# EasyEDA_Audio_Amp.net
KiCad netlist of a schematic drawn in EasyEDA Pro
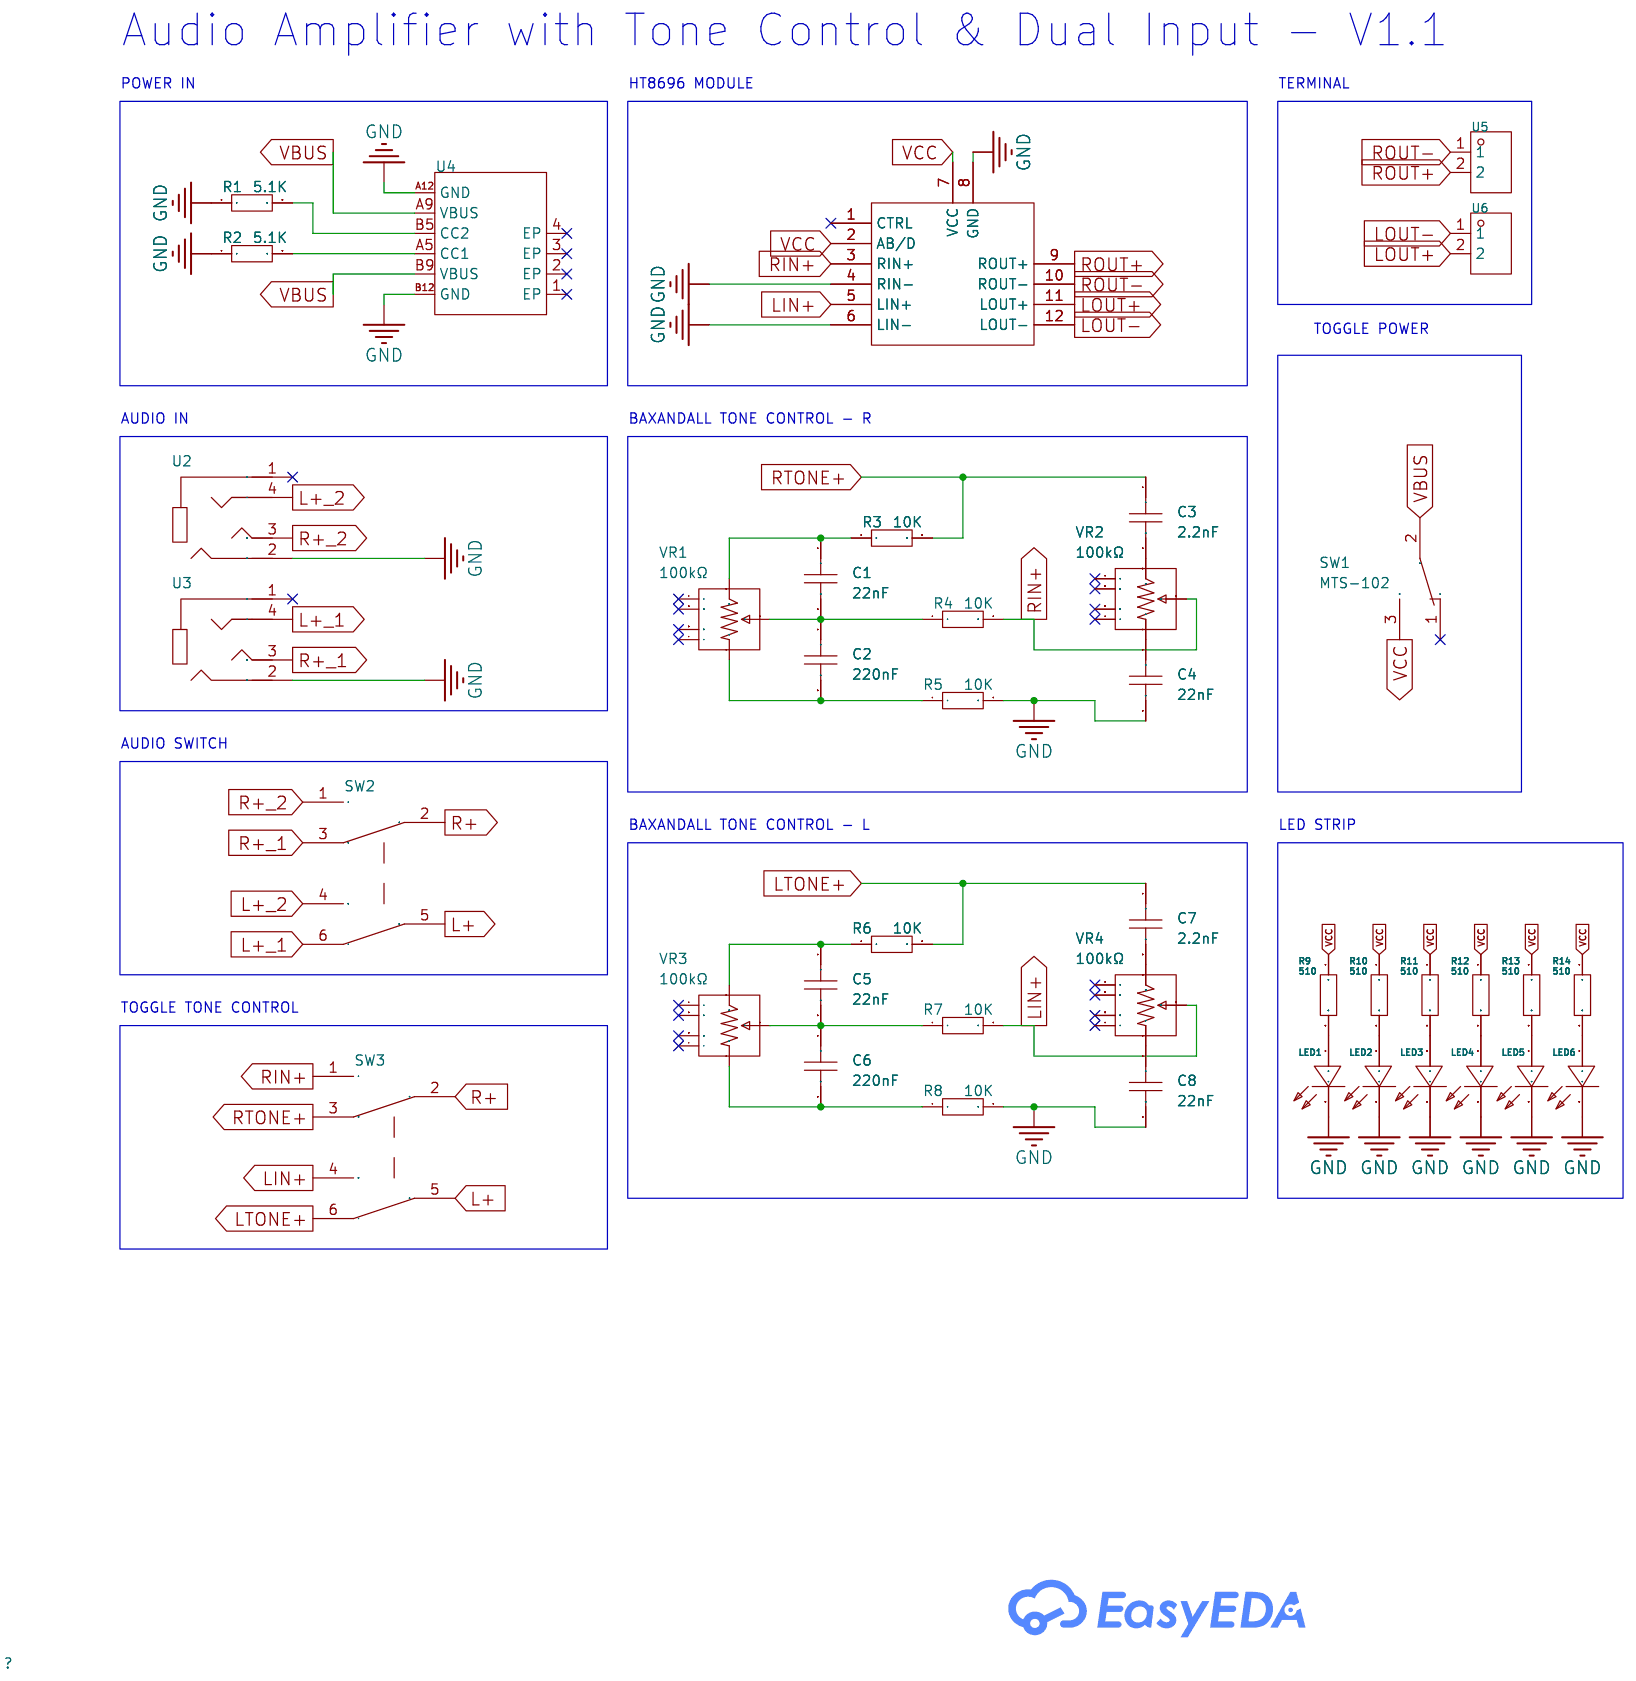
[diagram p0: schematic sheet]

(export (version "E")
  (design (tool "Eeschema 10.0.6"))
  (components
    (comp (ref "C1")
      (value "22nF")
      (footprint "easyedapro:C0603")
      (libsource (lib "easyedapro") (part "CAP_OLD"))
    )
    (comp (ref "C2")
      (value "220nF")
      (footprint "easyedapro:C0603")
      (libsource (lib "easyedapro") (part "CAP_OLD"))
    )
    (comp (ref "C3")
      (value "2.2nF")
      (footprint "easyedapro:C0603")
      (libsource (lib "easyedapro") (part "CAP_OLD"))
    )
    (comp (ref "C4")
      (value "22nF")
      (footprint "easyedapro:C0603")
      (libsource (lib "easyedapro") (part "CAP_OLD"))
    )
    (comp (ref "C5")
      (value "22nF")
      (footprint "easyedapro:C0603")
      (libsource (lib "easyedapro") (part "CAP_OLD"))
    )
    (comp (ref "C6")
      (value "220nF")
      (footprint "easyedapro:C0603")
      (libsource (lib "easyedapro") (part "CAP_OLD"))
    )
    (comp (ref "C7")
      (value "2.2nF")
      (footprint "easyedapro:C0603")
      (libsource (lib "easyedapro") (part "CAP_OLD"))
    )
    (comp (ref "C8")
      (value "22nF")
      (footprint "easyedapro:C0603")
      (libsource (lib "easyedapro") (part "CAP_OLD"))
    )
    (comp (ref "LED1")
      (value "KT-0805G")
      (footprint "easyedapro:LED0805-R-RD")
      (fields (field (name "Manufacturer") "KENTO"))
      (libsource (lib "easyedapro") (part "Led Rosso 0805"))
    )
    (comp (ref "LED2")
      (value "KT-0805G")
      (footprint "easyedapro:LED0805-R-RD")
      (fields (field (name "Manufacturer") "KENTO"))
      (libsource (lib "easyedapro") (part "Led Rosso 0805"))
    )
    (comp (ref "LED3")
      (value "KT-0805G")
      (footprint "easyedapro:LED0805-R-RD")
      (fields (field (name "Manufacturer") "KENTO"))
      (libsource (lib "easyedapro") (part "Led Rosso 0805"))
    )
    (comp (ref "LED4")
      (value "KT-0805G")
      (footprint "easyedapro:LED0805-R-RD")
      (fields (field (name "Manufacturer") "KENTO"))
      (libsource (lib "easyedapro") (part "Led Rosso 0805"))
    )
    (comp (ref "LED5")
      (value "KT-0805G")
      (footprint "easyedapro:LED0805-R-RD")
      (fields (field (name "Manufacturer") "KENTO"))
      (libsource (lib "easyedapro") (part "Led Rosso 0805"))
    )
    (comp (ref "LED6")
      (value "KT-0805G")
      (footprint "easyedapro:LED0805-R-RD")
      (fields (field (name "Manufacturer") "KENTO"))
      (libsource (lib "easyedapro") (part "Led Rosso 0805"))
    )
    (comp (ref "R1")
      (value "5.1K")
      (footprint "easyedapro:R0603")
      (fields
        (field (name "Manufacturer Part") "0805W8F2002T5E")
        (field (name "Manufacturer") "UNI-ROYAL(厚声)")
      )
      (libsource (lib "easyedapro") (part "Res"))
    )
    (comp (ref "R2")
      (value "5.1K")
      (footprint "easyedapro:R0603")
      (fields
        (field (name "Manufacturer Part") "0805W8F2002T5E")
        (field (name "Manufacturer") "UNI-ROYAL(厚声)")
      )
      (libsource (lib "easyedapro") (part "Res"))
    )
    (comp (ref "R3") (value "10K") (footprint "easyedapro:R0603") (libsource (lib "easyedapro") (part "Res")))
    (comp (ref "R4") (value "10K") (footprint "easyedapro:R0603") (libsource (lib "easyedapro") (part "Res")))
    (comp (ref "R5") (value "10K") (footprint "easyedapro:R0603") (libsource (lib "easyedapro") (part "Res")))
    (comp (ref "R6") (value "10K") (footprint "easyedapro:R0603") (libsource (lib "easyedapro") (part "Res")))
    (comp (ref "R7") (value "10K") (footprint "easyedapro:R0603") (libsource (lib "easyedapro") (part "Res")))
    (comp (ref "R8") (value "10K") (footprint "easyedapro:R0603") (libsource (lib "easyedapro") (part "Res")))
    (comp (ref "R9") (value "510") (footprint "easyedapro:R0603") (libsource (lib "easyedapro") (part "Res")))
    (comp (ref "R10")
      (value "510")
      (footprint "easyedapro:R0603")
      (libsource (lib "easyedapro") (part "Res"))
    )
    (comp (ref "R11")
      (value "510")
      (footprint "easyedapro:R0603")
      (libsource (lib "easyedapro") (part "Res"))
    )
    (comp (ref "R12")
      (value "510")
      (footprint "easyedapro:R0603")
      (libsource (lib "easyedapro") (part "Res"))
    )
    (comp (ref "R13")
      (value "510")
      (footprint "easyedapro:R0603")
      (libsource (lib "easyedapro") (part "Res"))
    )
    (comp (ref "R14")
      (value "510")
      (footprint "easyedapro:R0603")
      (libsource (lib "easyedapro") (part "Res"))
    )
    (comp (ref "SW1")
      (value "MTS-102")
      (footprint "easyedapro:MTS-102")
      (libsource (lib "easyedapro") (part "MTS-102"))
    )
    (comp (ref "SW2")
      (value "~")
      (footprint "easyedapro:MTS-202-A1")
      (libsource (lib "easyedapro") (part "MTS-202-A1_MOD"))
    )
    (comp (ref "SW3")
      (value "~")
      (footprint "easyedapro:MTS-202-A1")
      (libsource (lib "easyedapro") (part "MTS-202-A1_MOD"))
    )
    (comp (ref "U1") (value "~") (libsource (lib "easyedapro") (part "HT8696/7 Module")))
    (comp (ref "U2")
      (value "KH-PJ-320D-SMT")
      (footprint "easyedapro:AUDIO-SMD_KH-PJ-320D-SMT_1")
      (description "Connector Type:3.5mm Headphone Jack Contact Material:Tin bronze Contact Plating:Silver")
      (fields (field (name "Manufacturer") "kinghelm(金航标)"))
      (libsource (lib "easyedapro") (part "KH-PJ-320D-SMT"))
    )
    (comp (ref "U3")
      (value "KH-PJ-320D-SMT")
      (footprint "easyedapro:AUDIO-SMD_KH-PJ-320D-SMT_1")
      (description "Connector Type:3.5mm Headphone Jack Contact Material:Tin bronze Contact Plating:Silver")
      (fields (field (name "Manufacturer") "kinghelm(金航标)"))
      (libsource (lib "easyedapro") (part "KH-PJ-320D-SMT"))
    )
    (comp (ref "U4")
      (value "HX TYPE-C 6PIN DT")
      (footprint "easyedapro:TYPE-C-SMD_TYPE-C-31-M-16")
      (fields (field (name "Manufacturer") "hanxia(韩下)"))
      (libsource (lib "easyedapro") (part "HX TYPE-C 6PIN DT"))
    )
    (comp (ref "U5")
      (value "KF301-5.0-2P")
      (footprint "easyedapro:CONN-TH_P5.00_KF301-5.0-2P")
      (fields (field (name "Manufacturer") "KEFA(科发)"))
      (libsource (lib "easyedapro") (part "KF301-5.0-2P"))
    )
    (comp (ref "U6")
      (value "KF301-5.0-2P")
      (footprint "easyedapro:CONN-TH_P5.00_KF301-5.0-2P")
      (fields (field (name "Manufacturer") "KEFA(科发)"))
      (libsource (lib "easyedapro") (part "KF301-5.0-2P"))
    )
    (comp (ref "VR1")
      (value "100kΩ")
      (footprint "easyedapro:RES-ADJ-TH_PTA6043-2015DPB103")
      (description "Resistance:10kΩ Tolerance:±20% Tolerance:±20% Voltage Rating:200V Power(Watts):250mW")
      (fields (field (name "Manufacturer Part") "PTA6043-2015CPB103") (field (name "Manufacturer") "BOURNS"))
      (libsource (lib "easyedapro") (part "PTA6043-2015CPB103"))
    )
    (comp (ref "VR2")
      (value "100kΩ")
      (footprint "easyedapro:RES-ADJ-TH_PTA6043-2015DPB103")
      (description "Resistance:10kΩ Tolerance:±20% Tolerance:±20% Voltage Rating:200V Power(Watts):250mW")
      (fields (field (name "Manufacturer Part") "PTA6043-2015CPB103") (field (name "Manufacturer") "BOURNS"))
      (libsource (lib "easyedapro") (part "PTA6043-2015CPB103"))
    )
    (comp (ref "VR3")
      (value "100kΩ")
      (footprint "easyedapro:RES-ADJ-TH_PTA6043-2015DPB103")
      (description "Resistance:10kΩ Tolerance:±20% Tolerance:±20% Voltage Rating:200V Power(Watts):250mW")
      (fields (field (name "Manufacturer Part") "PTA6043-2015CPB103") (field (name "Manufacturer") "BOURNS"))
      (libsource (lib "easyedapro") (part "PTA6043-2015CPB103"))
    )
    (comp (ref "VR4")
      (value "100kΩ")
      (footprint "easyedapro:RES-ADJ-TH_PTA6043-2015DPB103")
      (description "Resistance:10kΩ Tolerance:±20% Tolerance:±20% Voltage Rating:200V Power(Watts):250mW")
      (fields (field (name "Manufacturer Part") "PTA6043-2015CPB103") (field (name "Manufacturer") "BOURNS"))
      (libsource (lib "easyedapro") (part "PTA6043-2015CPB103"))
    )
  )
  (nets
    (net (code "1") (name "GND") (class "Default")
      (node (ref "C4") (pin "2") (pinfunction "2_2") (pintype "input"))
      (node (ref "C8") (pin "2") (pinfunction "2_2") (pintype "input"))
      (node (ref "LED1") (pin "2") (pinfunction "K_2") (pintype "unspecified"))
      (node (ref "LED2") (pin "2") (pinfunction "K_2") (pintype "unspecified"))
      (node (ref "LED3") (pin "2") (pinfunction "K_2") (pintype "unspecified"))
      (node (ref "LED4") (pin "2") (pinfunction "K_2") (pintype "unspecified"))
      (node (ref "LED5") (pin "2") (pinfunction "K_2") (pintype "unspecified"))
      (node (ref "LED6") (pin "2") (pinfunction "K_2") (pintype "unspecified"))
      (node (ref "R1") (pin "1") (pinfunction "1_1") (pintype "input"))
      (node (ref "R2") (pin "1") (pinfunction "1_1") (pintype "input"))
      (node (ref "R5") (pin "2") (pinfunction "2_2") (pintype "input"))
      (node (ref "R8") (pin "2") (pinfunction "2_2") (pintype "input"))
      (node (ref "U1") (pin "4") (pinfunction "RIN-_4") (pintype "input"))
      (node (ref "U1") (pin "6") (pinfunction "LIN-_6") (pintype "input"))
      (node (ref "U1") (pin "8") (pinfunction "GND_8") (pintype "input"))
      (node (ref "U2") (pin "2") (pinfunction "2_2") (pintype "unspecified"))
      (node (ref "U3") (pin "2") (pinfunction "2_2") (pintype "unspecified"))
      (node (ref "U4") (pin "A12") (pinfunction "GND_A12") (pintype "unspecified"))
      (node (ref "U4") (pin "B12") (pinfunction "GND_B12") (pintype "unspecified"))
    )
    (net (code "2") (name "L+") (class "Default")
      (node (ref "SW2") (pin "5") (pinfunction "5_5") (pintype "input"))
      (node (ref "SW3") (pin "5") (pinfunction "5_5") (pintype "input"))
    )
    (net (code "3") (name "L+_1") (class "Default")
      (node (ref "SW2") (pin "6") (pinfunction "4_6") (pintype "input"))
      (node (ref "U3") (pin "4") (pinfunction "4_4") (pintype "unspecified"))
    )
    (net (code "4") (name "L+_2") (class "Default")
      (node (ref "SW2") (pin "4") (pinfunction "6_4") (pintype "input"))
      (node (ref "U2") (pin "4") (pinfunction "4_4") (pintype "unspecified"))
    )
    (net (code "5") (name "LIN+") (class "Default")
      (node (ref "R7") (pin "2") (pinfunction "2_2") (pintype "input"))
      (node (ref "SW3") (pin "4") (pinfunction "6_4") (pintype "input"))
      (node (ref "U1") (pin "5") (pinfunction "LIN+_5") (pintype "input"))
      (node (ref "VR4") (pin "2") (pinfunction "2_2") (pintype "unspecified"))
    )
    (net (code "6") (name "LOUT+") (class "Default")
      (node (ref "U1") (pin "11") (pinfunction "LOUT+_11") (pintype "input"))
      (node (ref "U6") (pin "2") (pinfunction "2_2") (pintype "input"))
    )
    (net (code "7") (name "LOUT-") (class "Default")
      (node (ref "U1") (pin "12") (pinfunction "LOUT-_12") (pintype "input"))
      (node (ref "U6") (pin "1") (pinfunction "1_1") (pintype "input"))
    )
    (net (code "8") (name "LTONE+") (class "Default")
      (node (ref "C7") (pin "1") (pinfunction "1_1") (pintype "input"))
      (node (ref "R6") (pin "2") (pinfunction "2_2") (pintype "input"))
      (node (ref "SW3") (pin "6") (pinfunction "4_6") (pintype "input"))
    )
    (net (code "9") (name "Net-(C1-Pad1)") (class "Default")
      (node (ref "C1") (pin "1") (pinfunction "1_1") (pintype "input"))
      (node (ref "R3") (pin "1") (pinfunction "1_1") (pintype "input"))
      (node (ref "VR1") (pin "3") (pinfunction "3_3") (pintype "unspecified"))
    )
    (net (code "10") (name "Net-(C1-Pad2)") (class "Default")
      (node (ref "C1") (pin "2") (pinfunction "2_2") (pintype "input"))
      (node (ref "C2") (pin "1") (pinfunction "1_1") (pintype "input"))
      (node (ref "R4") (pin "1") (pinfunction "1_1") (pintype "input"))
      (node (ref "VR1") (pin "2") (pinfunction "2_2") (pintype "unspecified"))
    )
    (net (code "11") (name "Net-(C2-Pad2)") (class "Default")
      (node (ref "C2") (pin "2") (pinfunction "2_2") (pintype "input"))
      (node (ref "R5") (pin "1") (pinfunction "1_1") (pintype "input"))
      (node (ref "VR1") (pin "1") (pinfunction "1_1") (pintype "unspecified"))
    )
    (net (code "12") (name "Net-(C3-Pad2)") (class "Default")
      (node (ref "C3") (pin "2") (pinfunction "2_2") (pintype "input"))
      (node (ref "VR2") (pin "3") (pinfunction "3_3") (pintype "unspecified"))
    )
    (net (code "13") (name "Net-(C4-Pad1)") (class "Default")
      (node (ref "C4") (pin "1") (pinfunction "1_1") (pintype "input"))
      (node (ref "VR2") (pin "1") (pinfunction "1_1") (pintype "unspecified"))
    )
    (net (code "14") (name "Net-(C5-Pad1)") (class "Default")
      (node (ref "C5") (pin "1") (pinfunction "1_1") (pintype "input"))
      (node (ref "R6") (pin "1") (pinfunction "1_1") (pintype "input"))
      (node (ref "VR3") (pin "3") (pinfunction "3_3") (pintype "unspecified"))
    )
    (net (code "15") (name "Net-(C5-Pad2)") (class "Default")
      (node (ref "C5") (pin "2") (pinfunction "2_2") (pintype "input"))
      (node (ref "C6") (pin "1") (pinfunction "1_1") (pintype "input"))
      (node (ref "R7") (pin "1") (pinfunction "1_1") (pintype "input"))
      (node (ref "VR3") (pin "2") (pinfunction "2_2") (pintype "unspecified"))
    )
    (net (code "16") (name "Net-(C6-Pad2)") (class "Default")
      (node (ref "C6") (pin "2") (pinfunction "2_2") (pintype "input"))
      (node (ref "R8") (pin "1") (pinfunction "1_1") (pintype "input"))
      (node (ref "VR3") (pin "1") (pinfunction "1_1") (pintype "unspecified"))
    )
    (net (code "17") (name "Net-(C7-Pad2)") (class "Default")
      (node (ref "C7") (pin "2") (pinfunction "2_2") (pintype "input"))
      (node (ref "VR4") (pin "3") (pinfunction "3_3") (pintype "unspecified"))
    )
    (net (code "18") (name "Net-(C8-Pad1)") (class "Default")
      (node (ref "C8") (pin "1") (pinfunction "1_1") (pintype "input"))
      (node (ref "VR4") (pin "1") (pinfunction "1_1") (pintype "unspecified"))
    )
    (net (code "19") (name "Net-(LED1-A)") (class "Default")
      (node (ref "LED1") (pin "1") (pinfunction "A_1") (pintype "unspecified"))
      (node (ref "R9") (pin "2") (pinfunction "2_2") (pintype "input"))
    )
    (net (code "20") (name "Net-(LED2-A)") (class "Default")
      (node (ref "LED2") (pin "1") (pinfunction "A_1") (pintype "unspecified"))
      (node (ref "R10") (pin "2") (pinfunction "2_2") (pintype "input"))
    )
    (net (code "21") (name "Net-(LED3-A)") (class "Default")
      (node (ref "LED3") (pin "1") (pinfunction "A_1") (pintype "unspecified"))
      (node (ref "R11") (pin "2") (pinfunction "2_2") (pintype "input"))
    )
    (net (code "22") (name "Net-(LED4-A)") (class "Default")
      (node (ref "LED4") (pin "1") (pinfunction "A_1") (pintype "unspecified"))
      (node (ref "R12") (pin "2") (pinfunction "2_2") (pintype "input"))
    )
    (net (code "23") (name "Net-(LED5-A)") (class "Default")
      (node (ref "LED5") (pin "1") (pinfunction "A_1") (pintype "unspecified"))
      (node (ref "R13") (pin "2") (pinfunction "2_2") (pintype "input"))
    )
    (net (code "24") (name "Net-(LED6-A)") (class "Default")
      (node (ref "LED6") (pin "1") (pinfunction "A_1") (pintype "unspecified"))
      (node (ref "R14") (pin "2") (pinfunction "2_2") (pintype "input"))
    )
    (net (code "25") (name "Net-(U4-CC1)") (class "Default")
      (node (ref "R2") (pin "2") (pinfunction "2_2") (pintype "input"))
      (node (ref "U4") (pin "A5") (pinfunction "CC1_A5") (pintype "unspecified"))
    )
    (net (code "26") (name "Net-(U4-CC2)") (class "Default")
      (node (ref "R1") (pin "2") (pinfunction "2_2") (pintype "input"))
      (node (ref "U4") (pin "B5") (pinfunction "CC2_B5") (pintype "unspecified"))
    )
    (net (code "27") (name "R+") (class "Default")
      (node (ref "SW2") (pin "2") (pinfunction "2_2") (pintype "input"))
      (node (ref "SW3") (pin "2") (pinfunction "2_2") (pintype "input"))
    )
    (net (code "28") (name "R+_1") (class "Default")
      (node (ref "SW2") (pin "3") (pinfunction "3_3") (pintype "input"))
      (node (ref "U3") (pin "3") (pinfunction "3_3") (pintype "unspecified"))
    )
    (net (code "29") (name "R+_2") (class "Default")
      (node (ref "SW2") (pin "1") (pinfunction "1_1") (pintype "input"))
      (node (ref "U2") (pin "3") (pinfunction "3_3") (pintype "unspecified"))
    )
    (net (code "30") (name "RIN+") (class "Default")
      (node (ref "R4") (pin "2") (pinfunction "2_2") (pintype "input"))
      (node (ref "SW3") (pin "1") (pinfunction "1_1") (pintype "input"))
      (node (ref "U1") (pin "3") (pinfunction "RIN+_3") (pintype "input"))
      (node (ref "VR2") (pin "2") (pinfunction "2_2") (pintype "unspecified"))
    )
    (net (code "31") (name "ROUT+") (class "Default")
      (node (ref "U1") (pin "9") (pinfunction "ROUT+_9") (pintype "input"))
      (node (ref "U5") (pin "2") (pinfunction "2_2") (pintype "input"))
    )
    (net (code "32") (name "ROUT-") (class "Default")
      (node (ref "U1") (pin "10") (pinfunction "ROUT-_10") (pintype "input"))
      (node (ref "U5") (pin "1") (pinfunction "1_1") (pintype "input"))
    )
    (net (code "33") (name "RTONE+") (class "Default")
      (node (ref "C3") (pin "1") (pinfunction "1_1") (pintype "input"))
      (node (ref "R3") (pin "2") (pinfunction "2_2") (pintype "input"))
      (node (ref "SW3") (pin "3") (pinfunction "3_3") (pintype "input"))
    )
    (net (code "34") (name "VBUS") (class "Default")
      (node (ref "SW1") (pin "2") (pinfunction "2_2") (pintype "input"))
      (node (ref "U4") (pin "A9") (pinfunction "VBUS_A9") (pintype "unspecified"))
      (node (ref "U4") (pin "B9") (pinfunction "VBUS_B9") (pintype "unspecified"))
    )
    (net (code "35") (name "VCC") (class "Default")
      (node (ref "R10") (pin "1") (pinfunction "1_1") (pintype "input"))
      (node (ref "R11") (pin "1") (pinfunction "1_1") (pintype "input"))
      (node (ref "R12") (pin "1") (pinfunction "1_1") (pintype "input"))
      (node (ref "R13") (pin "1") (pinfunction "1_1") (pintype "input"))
      (node (ref "R14") (pin "1") (pinfunction "1_1") (pintype "input"))
      (node (ref "R9") (pin "1") (pinfunction "1_1") (pintype "input"))
      (node (ref "SW1") (pin "3") (pinfunction "3_3") (pintype "input"))
      (node (ref "U1") (pin "2") (pinfunction "AB/D_2") (pintype "input"))
      (node (ref "U1") (pin "7") (pinfunction "VCC_7") (pintype "input"))
    )
    (net (code "36") (name "unconnected-(SW1-Pad1)") (class "Default")
      (node (ref "SW1") (pin "1") (pinfunction "1_1") (pintype "input+no_connect"))
    )
    (net (code "37") (name "unconnected-(U1-CTRL-Pad1)") (class "Default")
      (node (ref "U1") (pin "1") (pinfunction "CTRL_1") (pintype "input+no_connect"))
    )
    (net (code "38") (name "unconnected-(U2-Pad1)") (class "Default")
      (node (ref "U2") (pin "1") (pinfunction "1_1") (pintype "unspecified+no_connect"))
    )
    (net (code "39") (name "unconnected-(U3-Pad1)") (class "Default")
      (node (ref "U3") (pin "1") (pinfunction "1_1") (pintype "unspecified+no_connect"))
    )
    (net (code "40") (name "unconnected-(U4-EP-Pad1)") (class "Default")
      (node (ref "U4") (pin "1") (pinfunction "EP_1") (pintype "unspecified+no_connect"))
    )
    (net (code "41") (name "unconnected-(U4-EP-Pad2)") (class "Default")
      (node (ref "U4") (pin "2") (pinfunction "EP_2") (pintype "unspecified+no_connect"))
    )
    (net (code "42") (name "unconnected-(U4-EP-Pad3)") (class "Default")
      (node (ref "U4") (pin "3") (pinfunction "EP_3") (pintype "unspecified+no_connect"))
    )
    (net (code "43") (name "unconnected-(U4-EP-Pad4)") (class "Default")
      (node (ref "U4") (pin "4") (pinfunction "EP_4") (pintype "unspecified+no_connect"))
    )
    (net (code "44") (name "unconnected-(VR1-Pad4)") (class "Default")
      (node (ref "VR1") (pin "4") (pinfunction "4_4") (pintype "unspecified+no_connect"))
    )
    (net (code "45") (name "unconnected-(VR1-Pad5)") (class "Default")
      (node (ref "VR1") (pin "5") (pinfunction "5_5") (pintype "unspecified+no_connect"))
    )
    (net (code "46") (name "unconnected-(VR1-Pad6)") (class "Default")
      (node (ref "VR1") (pin "6") (pinfunction "6_6") (pintype "unspecified+no_connect"))
    )
    (net (code "47") (name "unconnected-(VR1-Pad7)") (class "Default")
      (node (ref "VR1") (pin "7") (pinfunction "7_7") (pintype "unspecified+no_connect"))
    )
    (net (code "48") (name "unconnected-(VR2-Pad4)") (class "Default")
      (node (ref "VR2") (pin "4") (pinfunction "4_4") (pintype "unspecified+no_connect"))
    )
    (net (code "49") (name "unconnected-(VR2-Pad5)") (class "Default")
      (node (ref "VR2") (pin "5") (pinfunction "5_5") (pintype "unspecified+no_connect"))
    )
    (net (code "50") (name "unconnected-(VR2-Pad6)") (class "Default")
      (node (ref "VR2") (pin "6") (pinfunction "6_6") (pintype "unspecified+no_connect"))
    )
    (net (code "51") (name "unconnected-(VR2-Pad7)") (class "Default")
      (node (ref "VR2") (pin "7") (pinfunction "7_7") (pintype "unspecified+no_connect"))
    )
    (net (code "52") (name "unconnected-(VR3-Pad4)") (class "Default")
      (node (ref "VR3") (pin "4") (pinfunction "4_4") (pintype "unspecified+no_connect"))
    )
    (net (code "53") (name "unconnected-(VR3-Pad5)") (class "Default")
      (node (ref "VR3") (pin "5") (pinfunction "5_5") (pintype "unspecified+no_connect"))
    )
    (net (code "54") (name "unconnected-(VR3-Pad6)") (class "Default")
      (node (ref "VR3") (pin "6") (pinfunction "6_6") (pintype "unspecified+no_connect"))
    )
    (net (code "55") (name "unconnected-(VR3-Pad7)") (class "Default")
      (node (ref "VR3") (pin "7") (pinfunction "7_7") (pintype "unspecified+no_connect"))
    )
    (net (code "56") (name "unconnected-(VR4-Pad4)") (class "Default")
      (node (ref "VR4") (pin "4") (pinfunction "4_4") (pintype "unspecified+no_connect"))
    )
    (net (code "57") (name "unconnected-(VR4-Pad5)") (class "Default")
      (node (ref "VR4") (pin "5") (pinfunction "5_5") (pintype "unspecified+no_connect"))
    )
    (net (code "58") (name "unconnected-(VR4-Pad6)") (class "Default")
      (node (ref "VR4") (pin "6") (pinfunction "6_6") (pintype "unspecified+no_connect"))
    )
    (net (code "59") (name "unconnected-(VR4-Pad7)") (class "Default")
      (node (ref "VR4") (pin "7") (pinfunction "7_7") (pintype "unspecified+no_connect"))
    )
  )
)
